# ProPrj_NE564_2025-07-16.net
KiCad netlist of a schematic drawn in EasyEDA Pro
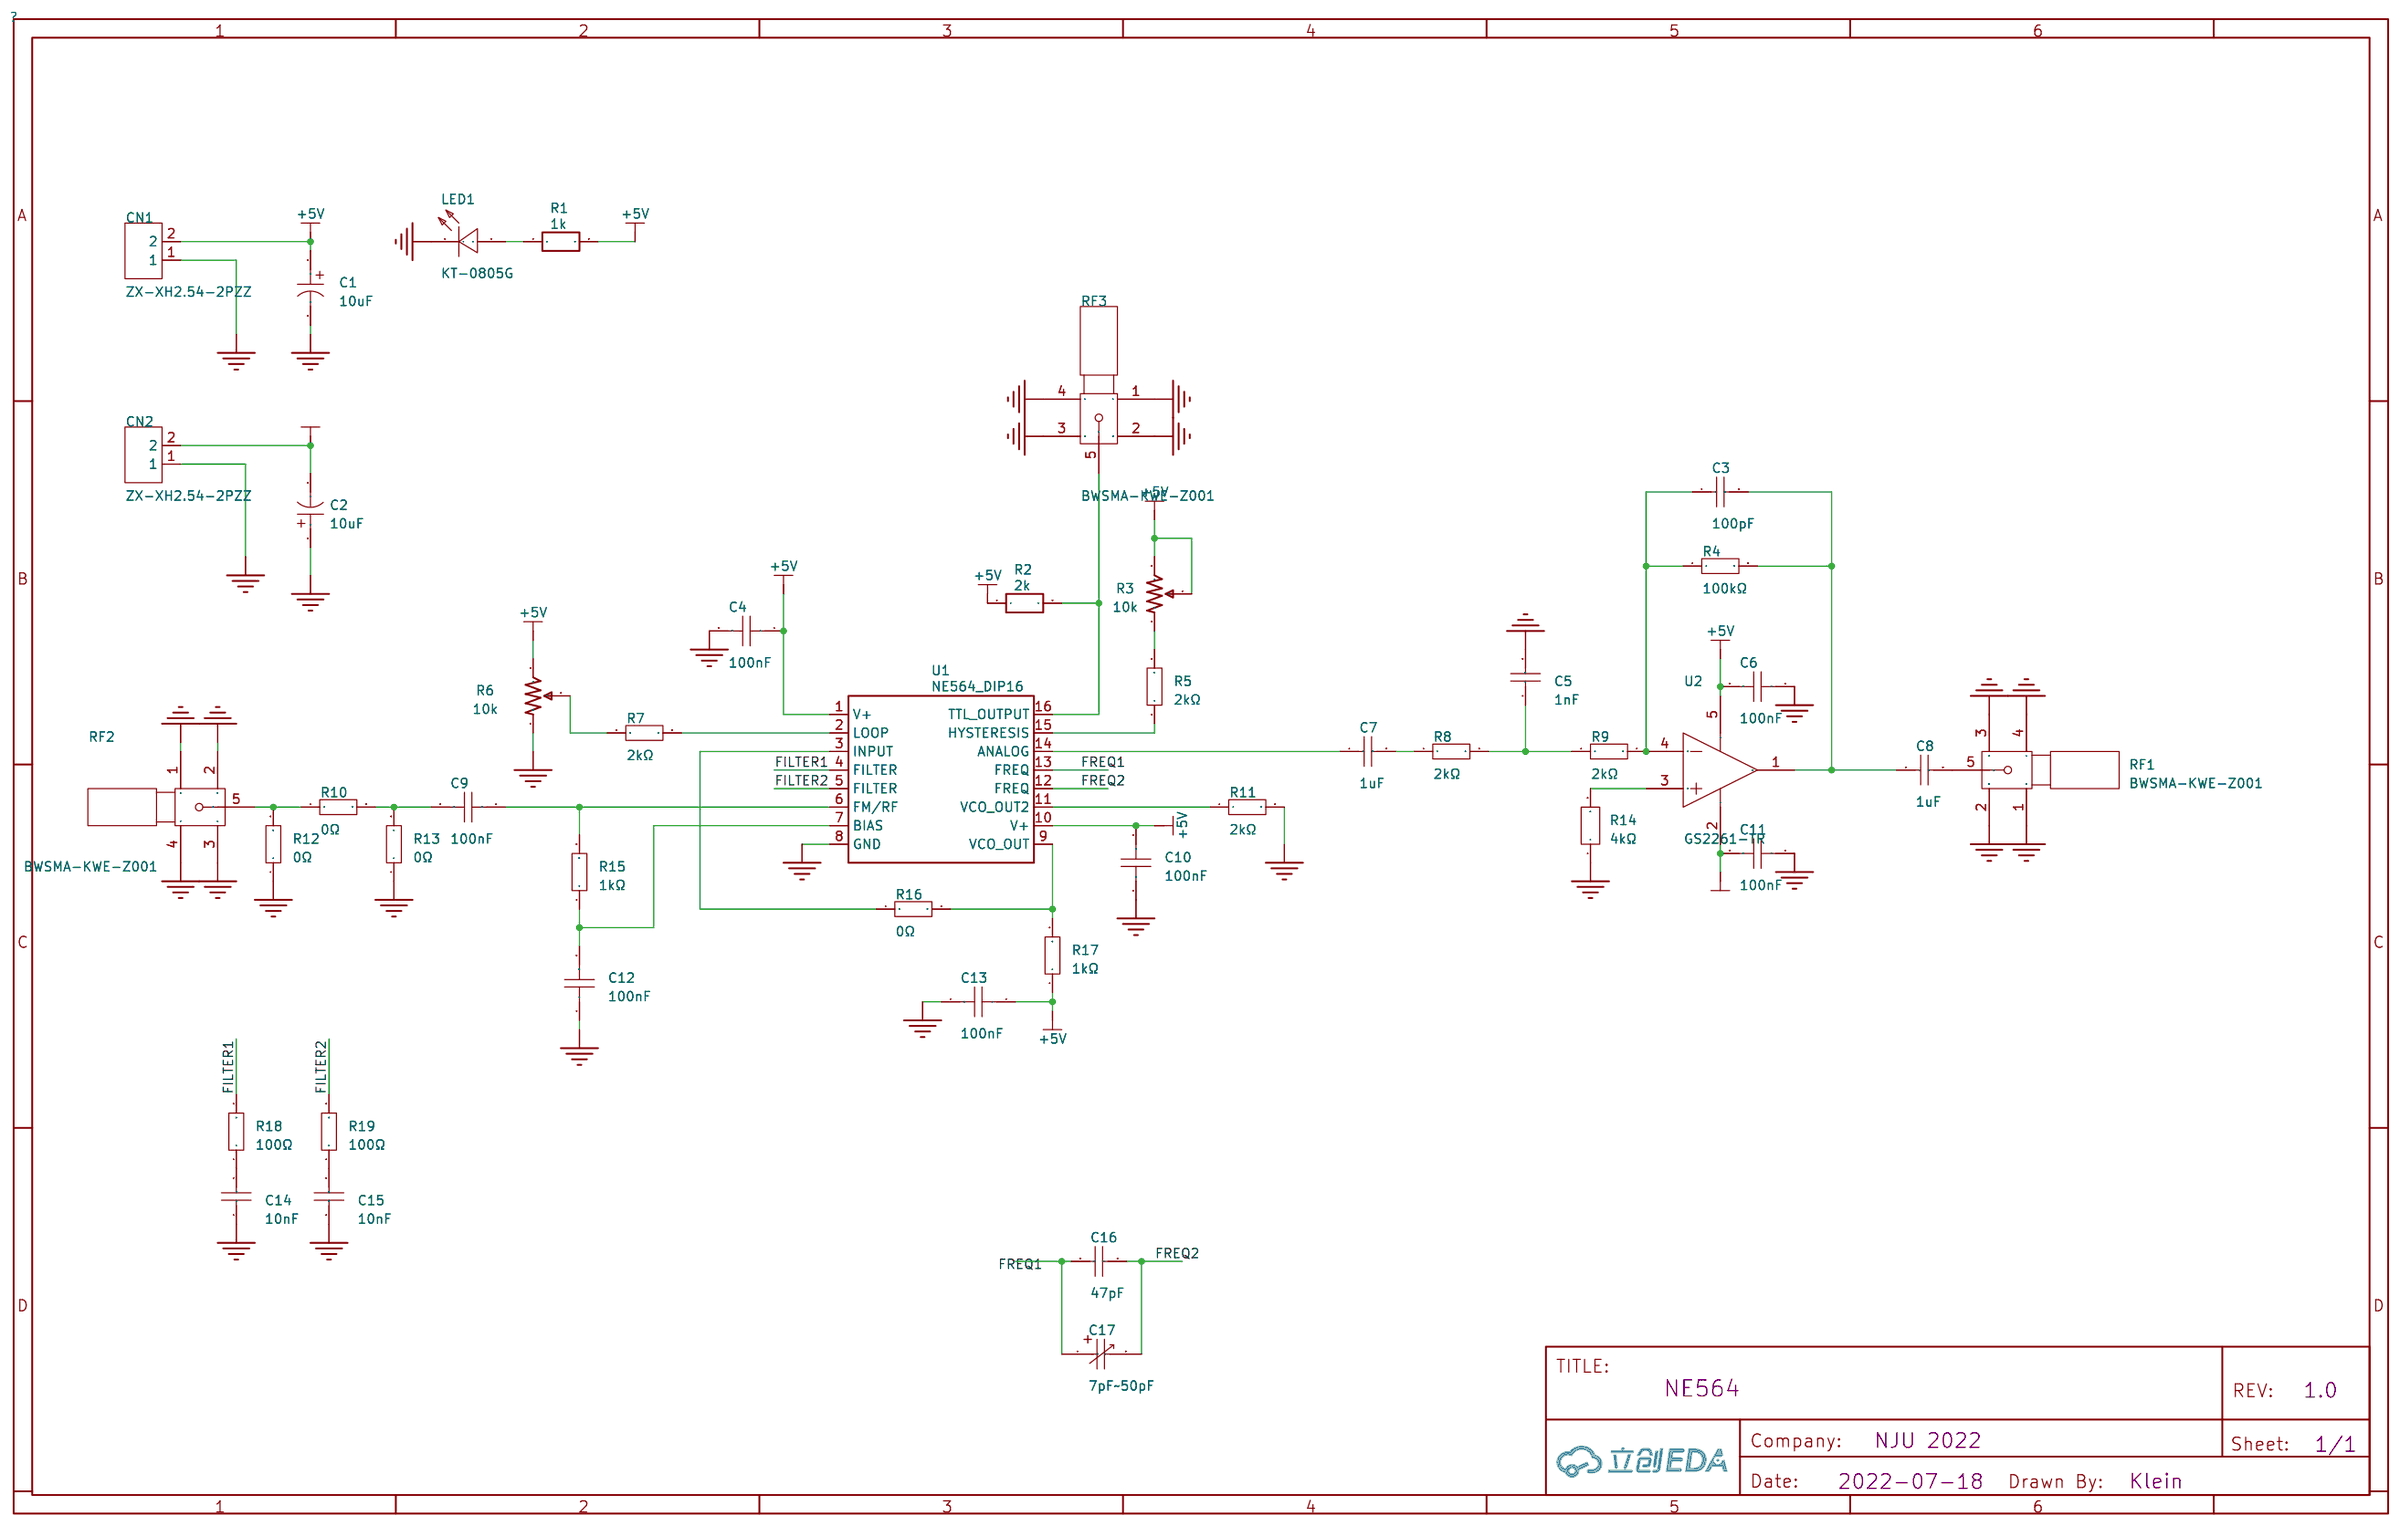
[diagram p0: schematic sheet]

(export (version "E")
  (design (tool "Eeschema 10.0.6"))
  (components
    (comp (ref "C1")
      (value "10uF")
      (footprint "easyedapro:CAP-SMD_BD5.0-L5.3-W5.3-LS6.0-FD")
      (description "容值:10uF;精度:±20%;额定电压:50V;纹波电流:18mA@120Hz;")
      (fields (field (name "Manufacturer Part") "JVJ50v10M5x5") (field (name "Manufacturer") "捷而瑞"))
      (libsource (lib "easyedapro") (part "JVJ50V10M5X5"))
    )
    (comp (ref "C2")
      (value "10uF")
      (footprint "easyedapro:CAP-SMD_BD5.0-L5.3-W5.3-LS6.0-FD")
      (description "容值:10uF;精度:±20%;额定电压:50V;纹波电流:18mA@120Hz;")
      (fields (field (name "Manufacturer Part") "JVJ50v10M5x5") (field (name "Manufacturer") "捷而瑞"))
      (libsource (lib "easyedapro") (part "JVJ50V10M5X5"))
    )
    (comp (ref "C3")
      (value "100pF")
      (footprint "easyedapro:C0603")
      (description "容值:100pF;精度:±5%;额定电压:50V;材质(温度系数):C0G;")
      (fields
        (field (name "Manufacturer Part") "CL10C101JB8NNNC")
        (field (name "Manufacturer") "SAMSUNG(三星)")
      )
      (libsource (lib "easyedapro") (part "CL10C101JB8NNNC"))
    )
    (comp (ref "C4")
      (value "100nF")
      (footprint "easyedapro:C0805")
      (description "容值:100nF;精度:±10%;额定电压:50V;材质(温度系数):X7R;")
      (fields
        (field (name "Manufacturer Part") "CC0805KRX7R9BB104")
        (field (name "Manufacturer") "YAGEO(国巨)")
      )
      (libsource (lib "easyedapro") (part "CC0805KRX7R9BB104"))
    )
    (comp (ref "C5")
      (value "1nF")
      (footprint "easyedapro:C0805")
      (description "容值:1nF;精度:±10%;额定电压:50V;材质(温度系数):X7R;")
      (fields
        (field (name "Manufacturer Part") "CL21B102KBCNNNC")
        (field (name "Manufacturer") "SAMSUNG(三星)")
      )
      (libsource (lib "easyedapro") (part "CL21B102KBCNNNC"))
    )
    (comp (ref "C6")
      (value "100nF")
      (footprint "easyedapro:C0805")
      (description "容值:100nF;精度:±10%;额定电压:50V;材质(温度系数):X7R;")
      (fields
        (field (name "Manufacturer Part") "CC0805KRX7R9BB104")
        (field (name "Manufacturer") "YAGEO(国巨)")
      )
      (libsource (lib "easyedapro") (part "CC0805KRX7R9BB104"))
    )
    (comp (ref "C7")
      (value "1uF")
      (footprint "easyedapro:C0805")
      (description "容值:1uF;精度:±10%;额定电压:50V;材质(温度系数):X7R;")
      (fields
        (field (name "Manufacturer Part") "CL21B105KBFNNNE")
        (field (name "Manufacturer") "SAMSUNG(三星)")
      )
      (libsource (lib "easyedapro") (part "CL21B105KBFNNNE"))
    )
    (comp (ref "C8")
      (value "1uF")
      (footprint "easyedapro:C0805")
      (description "容值:1uF;精度:±10%;额定电压:50V;材质(温度系数):X7R;")
      (fields
        (field (name "Manufacturer Part") "CL21B105KBFNNNE")
        (field (name "Manufacturer") "SAMSUNG(三星)")
      )
      (libsource (lib "easyedapro") (part "CL21B105KBFNNNE"))
    )
    (comp (ref "C9")
      (value "100nF")
      (footprint "easyedapro:C0805")
      (description "容值:100nF;精度:±10%;额定电压:50V;材质(温度系数):X7R;")
      (fields
        (field (name "Manufacturer Part") "CC0805KRX7R9BB104")
        (field (name "Manufacturer") "YAGEO(国巨)")
      )
      (libsource (lib "easyedapro") (part "CC0805KRX7R9BB104"))
    )
    (comp (ref "C10")
      (value "100nF")
      (footprint "easyedapro:C0805")
      (description "容值:100nF;精度:±10%;额定电压:50V;材质(温度系数):X7R;")
      (fields
        (field (name "Manufacturer Part") "CC0805KRX7R9BB104")
        (field (name "Manufacturer") "YAGEO(国巨)")
      )
      (libsource (lib "easyedapro") (part "CC0805KRX7R9BB104"))
    )
    (comp (ref "C11")
      (value "100nF")
      (footprint "easyedapro:C0805")
      (description "容值:100nF;精度:±10%;额定电压:50V;材质(温度系数):X7R;")
      (fields
        (field (name "Manufacturer Part") "CC0805KRX7R9BB104")
        (field (name "Manufacturer") "YAGEO(国巨)")
      )
      (libsource (lib "easyedapro") (part "CC0805KRX7R9BB104"))
    )
    (comp (ref "C12")
      (value "100nF")
      (footprint "easyedapro:C0805")
      (description "容值:100nF;精度:±10%;额定电压:50V;材质(温度系数):X7R;")
      (fields
        (field (name "Manufacturer Part") "CC0805KRX7R9BB104")
        (field (name "Manufacturer") "YAGEO(国巨)")
      )
      (libsource (lib "easyedapro") (part "CC0805KRX7R9BB104"))
    )
    (comp (ref "C13")
      (value "100nF")
      (footprint "easyedapro:C0805")
      (description "容值:100nF;精度:±10%;额定电压:50V;材质(温度系数):X7R;")
      (fields
        (field (name "Manufacturer Part") "CC0805KRX7R9BB104")
        (field (name "Manufacturer") "YAGEO(国巨)")
      )
      (libsource (lib "easyedapro") (part "CC0805KRX7R9BB104"))
    )
    (comp (ref "C14")
      (value "10nF")
      (footprint "easyedapro:C0805")
      (description "容值:10nF;精度:±10%;额定电压:50V;材质(温度系数):X7R;")
      (fields
        (field (name "Manufacturer Part") "CL21B103KBANNNC")
        (field (name "Manufacturer") "SAMSUNG(三星)")
      )
      (libsource (lib "easyedapro") (part "CL21B103KBANNNC"))
    )
    (comp (ref "C15")
      (value "10nF")
      (footprint "easyedapro:C0805")
      (description "容值:10nF;精度:±10%;额定电压:50V;材质(温度系数):X7R;")
      (fields
        (field (name "Manufacturer Part") "CL21B103KBANNNC")
        (field (name "Manufacturer") "SAMSUNG(三星)")
      )
      (libsource (lib "easyedapro") (part "CL21B103KBANNNC"))
    )
    (comp (ref "C16")
      (value "47pF")
      (footprint "easyedapro:C0805")
      (description "容值:47pF;精度:±5%;额定电压:50V;材质(温度系数):C0G;")
      (fields
        (field (name "Manufacturer Part") "CL21C470JBANNNC")
        (field (name "Manufacturer") "SAMSUNG(三星)")
      )
      (libsource (lib "easyedapro") (part "CL21C470JBANNNC"))
    )
    (comp (ref "C17")
      (value "7pF~50pF")
      (footprint "easyedapro:CAP-ADJ-SMD_L4.5-W4.2-L")
      (description "静电容量:7pF~50pF;静电容量公差:0%~+100%;额定电压:50V;电荷量:300@1MHz;")
      (fields (field (name "Manufacturer Part") "TZB4R500AB10R00") (field (name "Manufacturer") "muRata(村田)"))
      (libsource (lib "easyedapro") (part "TZB4R500AB10R00"))
    )
    (comp (ref "CN1")
      (value "ZX-XH2.54-2PZZ")
      (footprint "easyedapro:CONN-TH_2P-P2.50_HX25003-2A")
      (fields (field (name "Manufacturer") "Megastar(兆星)"))
      (libsource (lib "easyedapro") (part "ZX-XH2.54-2PZZ"))
    )
    (comp (ref "CN2")
      (value "ZX-XH2.54-2PZZ")
      (footprint "easyedapro:CONN-TH_2P-P2.50_HX25003-2A")
      (fields (field (name "Manufacturer") "Megastar(兆星)"))
      (libsource (lib "easyedapro") (part "ZX-XH2.54-2PZZ"))
    )
    (comp (ref "LED1")
      (value "KT-0805G")
      (footprint "easyedapro:LED0805-R-RD")
      (description "灯头类型:-;发光颜色:翠绿色;正向电压(VF):-;功率:-;正向电流:-;主波长:-;二极管配置:-;透镜颜色:-;色温:-;发光强度:-;发光角度:-;载带方式:-;工作温度:-;")
      (fields (field (name "Manufacturer") "KENTO"))
      (libsource (lib "easyedapro") (part "0805G (Green)"))
    )
    (comp (ref "R1")
      (value "1k")
      (footprint "easyedapro:R0805")
      (fields (field (name "Contributor") "LCEDA_Lib"))
      (libsource (lib "easyedapro") (part "1k"))
    )
    (comp (ref "R2")
      (value "2k")
      (footprint "easyedapro:R0805")
      (fields (field (name "Contributor") "LCEDA_Lib"))
      (libsource (lib "easyedapro") (part "2k"))
    )
    (comp (ref "R3")
      (value "10k")
      (footprint "easyedapro:RES-ADJ-TH_3296W")
      (fields (field (name "Contributor") "LCEDA_Lib"))
      (libsource (lib "easyedapro") (part "10k"))
    )
    (comp (ref "R4")
      (value "100kΩ")
      (footprint "easyedapro:R0805")
      (description "电阻类型:厚膜电阻;阻值:100kΩ;精度:±1%;功率:125mW;最大工作电压:150V;温度系数:±100ppm/°C;")
      (fields
        (field (name "Manufacturer Part") "0805W8F1003T5E")
        (field (name "Manufacturer") "UNI-ROYAL(厚声)")
      )
      (libsource (lib "easyedapro") (part "0805W8F1003T5E_C149504"))
    )
    (comp (ref "R5")
      (value "2kΩ")
      (footprint "easyedapro:R0805")
      (description "电阻类型:厚膜电阻;阻值:2kΩ;精度:±1%;功率:125mW;最大工作电压:150V;温度系数:±100ppm/°C;")
      (fields
        (field (name "Manufacturer Part") "0805W8F2001T5E")
        (field (name "Manufacturer") "UNI-ROYAL(厚声)")
      )
      (libsource (lib "easyedapro") (part "0805W8F2001T5E"))
    )
    (comp (ref "R6")
      (value "10k")
      (footprint "easyedapro:RES-ADJ-TH_3296W")
      (fields (field (name "Contributor") "LCEDA_Lib"))
      (libsource (lib "easyedapro") (part "10k"))
    )
    (comp (ref "R7")
      (value "2kΩ")
      (footprint "easyedapro:R0805")
      (description "电阻类型:厚膜电阻;阻值:2kΩ;精度:±1%;功率:125mW;最大工作电压:150V;温度系数:±100ppm/°C;")
      (fields
        (field (name "Manufacturer Part") "0805W8F2001T5E")
        (field (name "Manufacturer") "UNI-ROYAL(厚声)")
      )
      (libsource (lib "easyedapro") (part "0805W8F2001T5E"))
    )
    (comp (ref "R8")
      (value "2kΩ")
      (footprint "easyedapro:R0805")
      (description "电阻类型:厚膜电阻;阻值:2kΩ;精度:±1%;功率:125mW;最大工作电压:150V;温度系数:±100ppm/°C;")
      (fields
        (field (name "Manufacturer Part") "0805W8F2001T5E")
        (field (name "Manufacturer") "UNI-ROYAL(厚声)")
      )
      (libsource (lib "easyedapro") (part "0805W8F2001T5E"))
    )
    (comp (ref "R9")
      (value "2kΩ")
      (footprint "easyedapro:R0805")
      (description "电阻类型:厚膜电阻;阻值:2kΩ;精度:±1%;功率:125mW;最大工作电压:150V;温度系数:±100ppm/°C;")
      (fields
        (field (name "Manufacturer Part") "0805W8F2001T5E")
        (field (name "Manufacturer") "UNI-ROYAL(厚声)")
      )
      (libsource (lib "easyedapro") (part "0805W8F2001T5E"))
    )
    (comp (ref "R10")
      (value "0Ω")
      (footprint "easyedapro:R0805")
      (description "电阻类型:厚膜电阻;阻值:0Ω;精度:±1%;功率:125mW;最大工作电压:150V;温度系数:±800ppm/°C;")
      (fields
        (field (name "Manufacturer Part") "0805W8F0000T5E")
        (field (name "Manufacturer") "UNI-ROYAL(厚声)")
      )
      (libsource (lib "easyedapro") (part "0805W8F0000T5E"))
    )
    (comp (ref "R11")
      (value "2kΩ")
      (footprint "easyedapro:R0805")
      (description "电阻类型:厚膜电阻;阻值:2kΩ;精度:±1%;功率:125mW;最大工作电压:150V;温度系数:±100ppm/°C;")
      (fields
        (field (name "Manufacturer Part") "0805W8F2001T5E")
        (field (name "Manufacturer") "UNI-ROYAL(厚声)")
      )
      (libsource (lib "easyedapro") (part "0805W8F2001T5E"))
    )
    (comp (ref "R12")
      (value "0Ω")
      (footprint "easyedapro:R0805")
      (description "电阻类型:厚膜电阻;阻值:0Ω;精度:±1%;功率:125mW;最大工作电压:150V;温度系数:±800ppm/°C;")
      (fields
        (field (name "Manufacturer Part") "0805W8F0000T5E")
        (field (name "Manufacturer") "UNI-ROYAL(厚声)")
      )
      (libsource (lib "easyedapro") (part "0805W8F0000T5E"))
    )
    (comp (ref "R13")
      (value "0Ω")
      (footprint "easyedapro:R0805")
      (description "电阻类型:厚膜电阻;阻值:0Ω;精度:±1%;功率:125mW;最大工作电压:150V;温度系数:±800ppm/°C;")
      (fields
        (field (name "Manufacturer Part") "0805W8F0000T5E")
        (field (name "Manufacturer") "UNI-ROYAL(厚声)")
      )
      (libsource (lib "easyedapro") (part "0805W8F0000T5E"))
    )
    (comp (ref "R14")
      (value "4kΩ")
      (footprint "easyedapro:R0805")
      (description "电阻类型:薄膜电阻;阻值:4kΩ;精度:±1%;功率:125mW;最大工作电压:150V;温度系数:±25ppm/°C;")
      (fields (field (name "Manufacturer Part") "ARG05FTC4001N") (field (name "Manufacturer") "Viking(光颉)"))
      (libsource (lib "easyedapro") (part "ARG05FTC4001N"))
    )
    (comp (ref "R15")
      (value "1kΩ")
      (footprint "easyedapro:R0805")
      (description "电阻类型:厚膜电阻;阻值:1kΩ;精度:±1%;功率:125mW;最大工作电压:150V;温度系数:±100ppm/°C;")
      (fields
        (field (name "Manufacturer Part") "0805W8F1001T5E")
        (field (name "Manufacturer") "UNI-ROYAL(厚声)")
      )
      (libsource (lib "easyedapro") (part "0805W8F1001T5E"))
    )
    (comp (ref "R16")
      (value "0Ω")
      (footprint "easyedapro:R0805")
      (description "电阻类型:厚膜电阻;阻值:0Ω;精度:±1%;功率:125mW;最大工作电压:150V;温度系数:±800ppm/°C;")
      (fields
        (field (name "Manufacturer Part") "0805W8F0000T5E")
        (field (name "Manufacturer") "UNI-ROYAL(厚声)")
      )
      (libsource (lib "easyedapro") (part "0805W8F0000T5E"))
    )
    (comp (ref "R17")
      (value "1kΩ")
      (footprint "easyedapro:R0805")
      (description "电阻类型:厚膜电阻;阻值:1kΩ;精度:±1%;功率:125mW;最大工作电压:150V;温度系数:±100ppm/°C;")
      (fields
        (field (name "Manufacturer Part") "0805W8F1001T5E")
        (field (name "Manufacturer") "UNI-ROYAL(厚声)")
      )
      (libsource (lib "easyedapro") (part "0805W8F1001T5E"))
    )
    (comp (ref "R18")
      (value "100Ω")
      (footprint "easyedapro:R0805")
      (description "电阻类型:厚膜电阻;阻值:100Ω;精度:±1%;功率:125mW;最大工作电压:150V;温度系数:±100ppm/°C;")
      (fields
        (field (name "Manufacturer Part") "0805W8F1000T5E")
        (field (name "Manufacturer") "UNI-ROYAL(厚声)")
      )
      (libsource (lib "easyedapro") (part "0805W8F1000T5E"))
    )
    (comp (ref "R19")
      (value "100Ω")
      (footprint "easyedapro:R0805")
      (description "电阻类型:厚膜电阻;阻值:100Ω;精度:±1%;功率:125mW;最大工作电压:150V;温度系数:±100ppm/°C;")
      (fields
        (field (name "Manufacturer Part") "0805W8F1000T5E")
        (field (name "Manufacturer") "UNI-ROYAL(厚声)")
      )
      (libsource (lib "easyedapro") (part "0805W8F1000T5E"))
    )
    (comp (ref "RF1")
      (value "BWSMA-KWE-Z001")
      (footprint "easyedapro:SMA-TH_BWSMA-KWE-Z001")
      (fields (field (name "Manufacturer") "BAT WIRELESS(蝙蝠无线)"))
      (libsource (lib "easyedapro") (part "BWSMA-KWE-Z001"))
    )
    (comp (ref "RF2")
      (value "BWSMA-KWE-Z001")
      (footprint "easyedapro:SMA-TH_BWSMA-KWE-Z001")
      (fields (field (name "Manufacturer") "BAT WIRELESS(蝙蝠无线)"))
      (libsource (lib "easyedapro") (part "BWSMA-KWE-Z001"))
    )
    (comp (ref "RF3")
      (value "BWSMA-KWE-Z001")
      (footprint "easyedapro:SMA-TH_BWSMA-KWE-Z001")
      (fields (field (name "Manufacturer") "BAT WIRELESS(蝙蝠无线)"))
      (libsource (lib "easyedapro") (part "BWSMA-KWE-Z001"))
    )
    (comp (ref "U1")
      (value "NE564_DIP16")
      (footprint "easyedapro:DIP16")
      (fields
        (field (name "Manufacturer Part") "NE564")
        (field (name "Manufacturer") "Shenzhen Nsiway Tech")
        (field (name "Contributor") "Raincorn")
      )
      (libsource (lib "easyedapro") (part "NE564_DIP16"))
    )
    (comp (ref "U2")
      (value "GS2261-TR")
      (footprint "easyedapro:SOT-23-5_L3.0-W1.7-P0.95-LS2.8-BL")
      (description "放大器数:单路;轨到轨:-;增益带宽积(GBP):-;输入失调电压(Vos):100uV;压摆率(SR):23V/us;输入偏置电流(Ib):100pA;")
      (fields (field (name "Manufacturer") "Gainsil(聚洵)"))
      (libsource (lib "easyedapro") (part "GS2261-TR"))
    )
  )
  (nets
    (net (code "1") (name "+5V") (class "Default")
      (node (ref "C1") (pin "1") (pinfunction "1_1") (pintype "input"))
      (node (ref "C10") (pin "2") (pinfunction "2_2") (pintype "unspecified"))
      (node (ref "C13") (pin "1") (pinfunction "1_1") (pintype "unspecified"))
      (node (ref "C4") (pin "1") (pinfunction "1_1") (pintype "unspecified"))
      (node (ref "C6") (pin "2") (pinfunction "2_2") (pintype "unspecified"))
      (node (ref "CN1") (pin "2") (pinfunction "2_2") (pintype "unspecified"))
      (node (ref "R1") (pin "2") (pinfunction "2_2") (pintype "unspecified"))
      (node (ref "R17") (pin "1") (pinfunction "1_1") (pintype "input"))
      (node (ref "R2") (pin "1") (pinfunction "1_1") (pintype "unspecified"))
      (node (ref "R3") (pin "2") (pinfunction "2_2") (pintype "unspecified"))
      (node (ref "R3") (pin "3") (pinfunction "3_3") (pintype "unspecified"))
      (node (ref "R6") (pin "3") (pinfunction "3_3") (pintype "unspecified"))
      (node (ref "U1") (pin "1") (pinfunction "V+_1") (pintype "unspecified"))
      (node (ref "U1") (pin "10") (pinfunction "V+_10") (pintype "unspecified"))
      (node (ref "U2") (pin "5") (pinfunction "V+_5") (pintype "unspecified"))
    )
    (net (code "2") (name "-5V") (class "Default")
      (node (ref "C11") (pin "2") (pinfunction "2_2") (pintype "unspecified"))
      (node (ref "C2") (pin "2") (pinfunction "2_2") (pintype "input"))
      (node (ref "CN2") (pin "2") (pinfunction "2_2") (pintype "unspecified"))
      (node (ref "U2") (pin "2") (pinfunction "V-_2") (pintype "unspecified"))
    )
    (net (code "3") (name "/FILTER1") (class "Default")
      (node (ref "R18") (pin "2") (pinfunction "2_2") (pintype "input"))
      (node (ref "U1") (pin "4") (pinfunction "FILTER_4") (pintype "unspecified"))
    )
    (net (code "4") (name "/FILTER2") (class "Default")
      (node (ref "R19") (pin "2") (pinfunction "2_2") (pintype "input"))
      (node (ref "U1") (pin "5") (pinfunction "FILTER_5") (pintype "unspecified"))
    )
    (net (code "5") (name "/FREQ1") (class "Default")
      (node (ref "C16") (pin "1") (pinfunction "1_1") (pintype "input"))
      (node (ref "C17") (pin "1") (pinfunction "1_1") (pintype "unspecified"))
      (node (ref "U1") (pin "13") (pinfunction "FREQ_13") (pintype "unspecified"))
    )
    (net (code "6") (name "/FREQ2") (class "Default")
      (node (ref "C16") (pin "2") (pinfunction "2_2") (pintype "input"))
      (node (ref "C17") (pin "2") (pinfunction "2_2") (pintype "unspecified"))
      (node (ref "U1") (pin "12") (pinfunction "FREQ_12") (pintype "unspecified"))
    )
    (net (code "7") (name "GND") (class "Default")
      (node (ref "C1") (pin "2") (pinfunction "2_2") (pintype "input"))
      (node (ref "C10") (pin "1") (pinfunction "1_1") (pintype "unspecified"))
      (node (ref "C11") (pin "1") (pinfunction "1_1") (pintype "unspecified"))
      (node (ref "C12") (pin "1") (pinfunction "1_1") (pintype "unspecified"))
      (node (ref "C13") (pin "2") (pinfunction "2_2") (pintype "unspecified"))
      (node (ref "C14") (pin "1") (pinfunction "1_1") (pintype "input"))
      (node (ref "C15") (pin "1") (pinfunction "1_1") (pintype "input"))
      (node (ref "C2") (pin "1") (pinfunction "1_1") (pintype "input"))
      (node (ref "C4") (pin "2") (pinfunction "2_2") (pintype "unspecified"))
      (node (ref "C5") (pin "2") (pinfunction "2_2") (pintype "input"))
      (node (ref "C6") (pin "1") (pinfunction "1_1") (pintype "unspecified"))
      (node (ref "CN1") (pin "1") (pinfunction "1_1") (pintype "unspecified"))
      (node (ref "CN2") (pin "1") (pinfunction "1_1") (pintype "unspecified"))
      (node (ref "LED1") (pin "2") (pinfunction "K_2") (pintype "unspecified"))
      (node (ref "R11") (pin "2") (pinfunction "2_2") (pintype "input"))
      (node (ref "R12") (pin "1") (pinfunction "1_1") (pintype "input"))
      (node (ref "R13") (pin "1") (pinfunction "1_1") (pintype "input"))
      (node (ref "R14") (pin "1") (pinfunction "1_1") (pintype "unspecified"))
      (node (ref "R6") (pin "1") (pinfunction "1_1") (pintype "unspecified"))
      (node (ref "RF1") (pin "1") (pinfunction "1_1") (pintype "unspecified"))
      (node (ref "RF1") (pin "2") (pinfunction "2_2") (pintype "unspecified"))
      (node (ref "RF1") (pin "3") (pinfunction "3_3") (pintype "unspecified"))
      (node (ref "RF1") (pin "4") (pinfunction "4_4") (pintype "unspecified"))
      (node (ref "RF2") (pin "1") (pinfunction "1_1") (pintype "unspecified"))
      (node (ref "RF2") (pin "2") (pinfunction "2_2") (pintype "unspecified"))
      (node (ref "RF2") (pin "3") (pinfunction "3_3") (pintype "unspecified"))
      (node (ref "RF2") (pin "4") (pinfunction "4_4") (pintype "unspecified"))
      (node (ref "RF3") (pin "1") (pinfunction "1_1") (pintype "unspecified"))
      (node (ref "RF3") (pin "2") (pinfunction "2_2") (pintype "unspecified"))
      (node (ref "RF3") (pin "3") (pinfunction "3_3") (pintype "unspecified"))
      (node (ref "RF3") (pin "4") (pinfunction "4_4") (pintype "unspecified"))
      (node (ref "U1") (pin "8") (pinfunction "GND_8") (pintype "unspecified"))
    )
    (net (code "8") (name "Net-(C5-Pad1)") (class "Default")
      (node (ref "C5") (pin "1") (pinfunction "1_1") (pintype "input"))
      (node (ref "R8") (pin "2") (pinfunction "2_2") (pintype "input"))
      (node (ref "R9") (pin "1") (pinfunction "1_1") (pintype "input"))
    )
    (net (code "9") (name "Net-(C7-Pad2)") (class "Default")
      (node (ref "C7") (pin "2") (pinfunction "2_2") (pintype "input"))
      (node (ref "R8") (pin "1") (pinfunction "1_1") (pintype "input"))
    )
    (net (code "10") (name "Net-(C8-Pad2)") (class "Default")
      (node (ref "C8") (pin "2") (pinfunction "2_2") (pintype "input"))
      (node (ref "RF1") (pin "5") (pinfunction "5_5") (pintype "unspecified"))
    )
    (net (code "11") (name "Net-(C9-Pad2)") (class "Default")
      (node (ref "C9") (pin "2") (pinfunction "2_2") (pintype "unspecified"))
      (node (ref "R10") (pin "2") (pinfunction "2_2") (pintype "input"))
      (node (ref "R13") (pin "2") (pinfunction "2_2") (pintype "input"))
    )
    (net (code "12") (name "Net-(C14-Pad2)") (class "Default")
      (node (ref "C14") (pin "2") (pinfunction "2_2") (pintype "input"))
      (node (ref "R18") (pin "1") (pinfunction "1_1") (pintype "input"))
    )
    (net (code "13") (name "Net-(C15-Pad2)") (class "Default")
      (node (ref "C15") (pin "2") (pinfunction "2_2") (pintype "input"))
      (node (ref "R19") (pin "1") (pinfunction "1_1") (pintype "input"))
    )
    (net (code "14") (name "Net-(LED1-A)") (class "Default")
      (node (ref "LED1") (pin "1") (pinfunction "A_1") (pintype "unspecified"))
      (node (ref "R1") (pin "1") (pinfunction "1_1") (pintype "unspecified"))
    )
    (net (code "15") (name "Net-(R3-Pad1)") (class "Default")
      (node (ref "R3") (pin "1") (pinfunction "1_1") (pintype "unspecified"))
      (node (ref "R5") (pin "2") (pinfunction "2_2") (pintype "input"))
    )
    (net (code "16") (name "Net-(R6-Pad2)") (class "Default")
      (node (ref "R6") (pin "2") (pinfunction "2_2") (pintype "unspecified"))
      (node (ref "R7") (pin "1") (pinfunction "1_1") (pintype "input"))
    )
    (net (code "17") (name "Net-(R10-Pad1)") (class "Default")
      (node (ref "R10") (pin "1") (pinfunction "1_1") (pintype "input"))
      (node (ref "R12") (pin "2") (pinfunction "2_2") (pintype "input"))
      (node (ref "RF2") (pin "5") (pinfunction "5_5") (pintype "unspecified"))
    )
    (net (code "18") (name "Net-(U1-ANALOG)") (class "Default")
      (node (ref "C7") (pin "1") (pinfunction "1_1") (pintype "input"))
      (node (ref "U1") (pin "14") (pinfunction "ANALOG_14") (pintype "unspecified"))
    )
    (net (code "19") (name "Net-(U1-BIAS)") (class "Default")
      (node (ref "C12") (pin "2") (pinfunction "2_2") (pintype "unspecified"))
      (node (ref "R15") (pin "1") (pinfunction "1_1") (pintype "input"))
      (node (ref "U1") (pin "7") (pinfunction "BIAS_7") (pintype "unspecified"))
    )
    (net (code "20") (name "Net-(U1-FM{slash}RF)") (class "Default")
      (node (ref "C9") (pin "1") (pinfunction "1_1") (pintype "unspecified"))
      (node (ref "R15") (pin "2") (pinfunction "2_2") (pintype "input"))
      (node (ref "U1") (pin "6") (pinfunction "FM/RF_6") (pintype "unspecified"))
    )
    (net (code "21") (name "Net-(U1-HYSTERESIS)") (class "Default")
      (node (ref "R5") (pin "1") (pinfunction "1_1") (pintype "input"))
      (node (ref "U1") (pin "15") (pinfunction "HYSTERESIS_15") (pintype "unspecified"))
    )
    (net (code "22") (name "Net-(U1-INPUT)") (class "Default")
      (node (ref "R16") (pin "1") (pinfunction "1_1") (pintype "input"))
      (node (ref "U1") (pin "3") (pinfunction "INPUT_3") (pintype "unspecified"))
    )
    (net (code "23") (name "Net-(U1-LOOP)") (class "Default")
      (node (ref "R7") (pin "2") (pinfunction "2_2") (pintype "input"))
      (node (ref "U1") (pin "2") (pinfunction "LOOP_2") (pintype "unspecified"))
    )
    (net (code "24") (name "Net-(U1-TTL_OUTPUT)") (class "Default")
      (node (ref "R2") (pin "2") (pinfunction "2_2") (pintype "unspecified"))
      (node (ref "RF3") (pin "5") (pinfunction "5_5") (pintype "unspecified"))
      (node (ref "U1") (pin "16") (pinfunction "TTL_OUTPUT_16") (pintype "unspecified"))
    )
    (net (code "25") (name "Net-(U1-VCO_OUT)") (class "Default")
      (node (ref "R16") (pin "2") (pinfunction "2_2") (pintype "input"))
      (node (ref "R17") (pin "2") (pinfunction "2_2") (pintype "input"))
      (node (ref "U1") (pin "9") (pinfunction "VCO_OUT_9") (pintype "unspecified"))
    )
    (net (code "26") (name "Net-(U1-VCO_OUT2)") (class "Default")
      (node (ref "R11") (pin "1") (pinfunction "1_1") (pintype "input"))
      (node (ref "U1") (pin "11") (pinfunction "VCO_OUT2_11") (pintype "unspecified"))
    )
    (net (code "27") (name "Net-(U2-IN+)") (class "Default")
      (node (ref "R14") (pin "2") (pinfunction "2_2") (pintype "unspecified"))
      (node (ref "U2") (pin "3") (pinfunction "IN+_3") (pintype "unspecified"))
    )
    (net (code "28") (name "Net-(U2-IN-)") (class "Default")
      (node (ref "C3") (pin "1") (pinfunction "1_1") (pintype "input"))
      (node (ref "R4") (pin "1") (pinfunction "1_1") (pintype "unspecified"))
      (node (ref "R9") (pin "2") (pinfunction "2_2") (pintype "input"))
      (node (ref "U2") (pin "4") (pinfunction "IN-_4") (pintype "unspecified"))
    )
    (net (code "29") (name "Net-(U2-OUT)") (class "Default")
      (node (ref "C3") (pin "2") (pinfunction "2_2") (pintype "input"))
      (node (ref "C8") (pin "1") (pinfunction "1_1") (pintype "input"))
      (node (ref "R4") (pin "2") (pinfunction "2_2") (pintype "unspecified"))
      (node (ref "U2") (pin "1") (pinfunction "OUT_1") (pintype "output"))
    )
  )
)
